# Task_10_1DHD_02_2021-05-30.net
KiCad netlist of a schematic drawn in EasyEDA
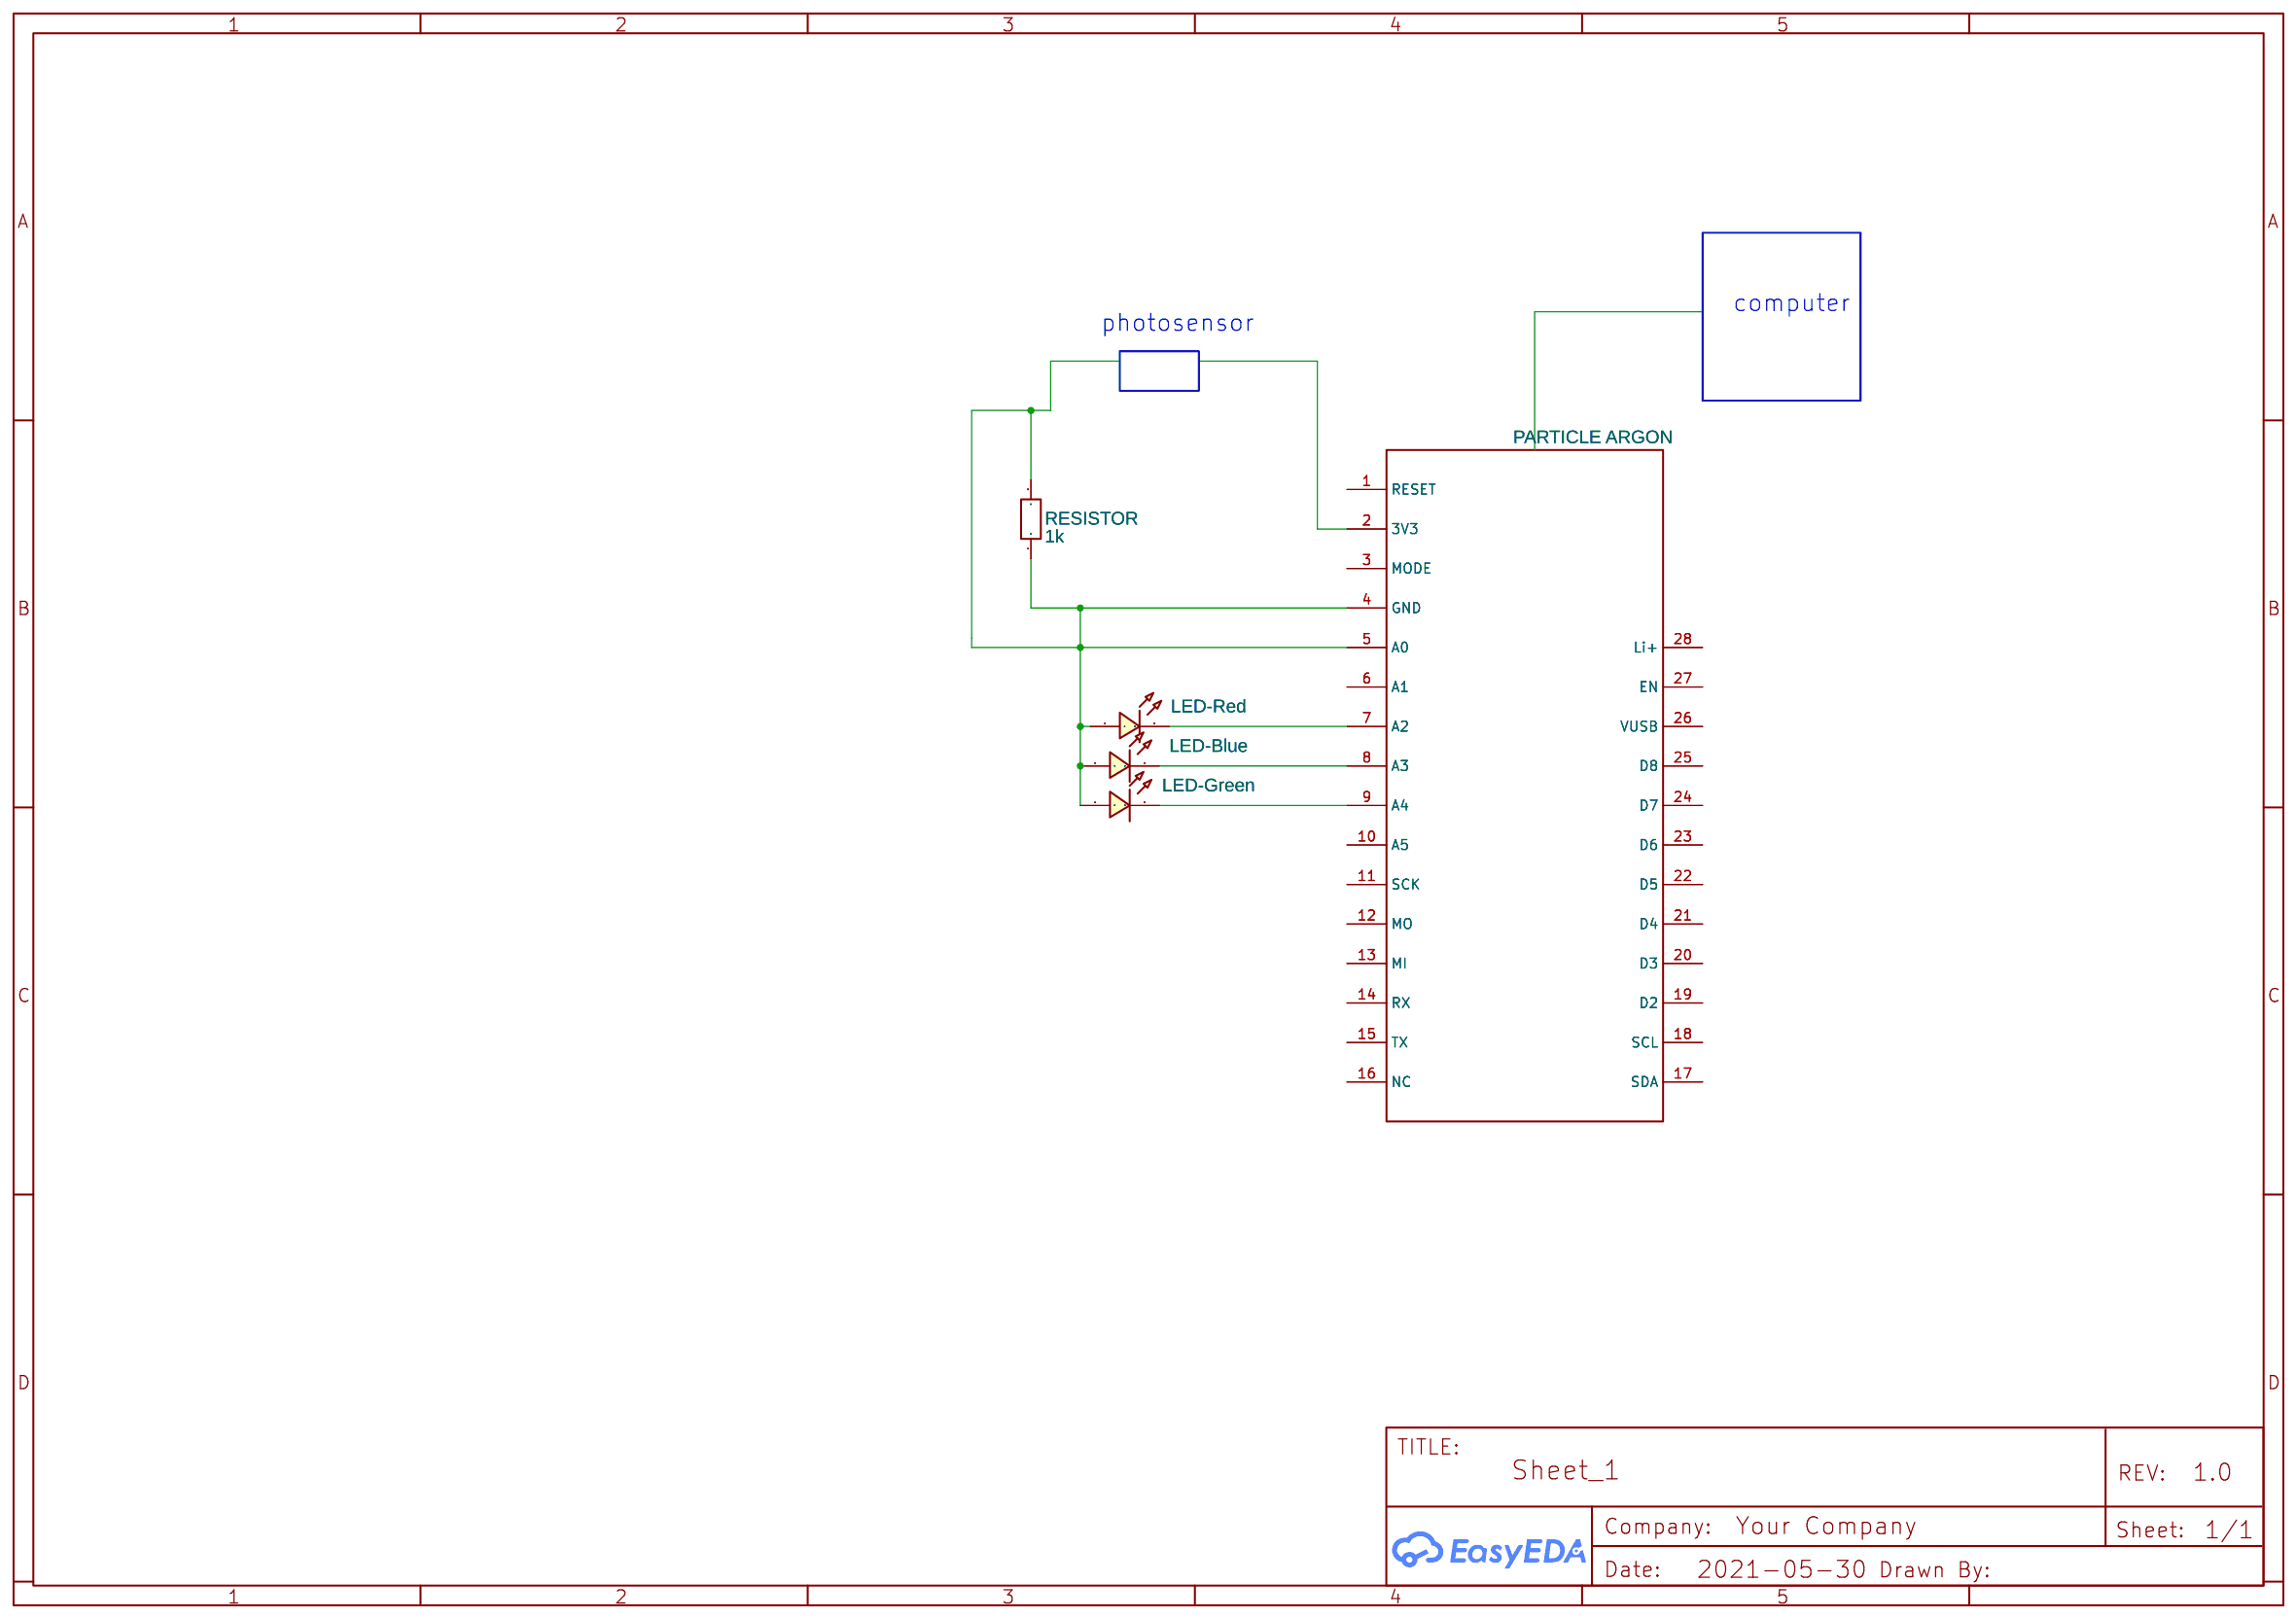
[diagram p0: schematic sheet]

(export (version "E")
  (design (tool "Eeschema 10.0.6"))
  (components
    (comp (ref "LED2")
      (value "LED-Green")
      (fields
        (field (name "BOM_Manufacturer Part") "19-217/R6C-AL1M2VY/3T")
        (field (name "BOM_Supplier Part") "C72044")
      )
      (libsource (lib "") (part "LED-0603_R"))
    )
    (comp (ref "LED3")
      (value "LED-Blue")
      (fields
        (field (name "BOM_Manufacturer Part") "19-217/R6C-AL1M2VY/3T")
        (field (name "BOM_Supplier Part") "C72044")
      )
      (libsource (lib "") (part "LED-0603_R"))
    )
    (comp (ref "LED4")
      (value "LED-Red")
      (fields
        (field (name "BOM_Manufacturer Part") "19-217/R6C-AL1M2VY/3T")
        (field (name "BOM_Supplier Part") "C72044")
      )
      (libsource (lib "") (part "LED-0603_R"))
    )
    (comp (ref "RESISTOR") (value "1k") (libsource (lib "") (part "R_0603_EU")))
    (comp (ref "U1") (value "PARTICLE ARGON") (libsource (lib "") (part "PARTICLE ARGON")))
  )
  (nets
    (net (code "1") (name "Net-(U1-A0)") (class "Default")
      (node (ref "LED2") (pin "1") (pinfunction "1_1") (pintype "unspecified"))
      (node (ref "LED3") (pin "1") (pinfunction "1_1") (pintype "unspecified"))
      (node (ref "LED4") (pin "1") (pinfunction "1_1") (pintype "unspecified"))
      (node (ref "RESISTOR") (pin "1") (pinfunction "1_1") (pintype "unspecified"))
      (node (ref "RESISTOR") (pin "2") (pinfunction "2_2") (pintype "unspecified"))
      (node (ref "U1") (pin "4") (pinfunction "GND_4") (pintype "unspecified"))
      (node (ref "U1") (pin "5") (pinfunction "A0_5") (pintype "unspecified"))
    )
    (net (code "2") (name "Net-(U1-A2)") (class "Default")
      (node (ref "LED4") (pin "2") (pinfunction "2_2") (pintype "unspecified"))
      (node (ref "U1") (pin "7") (pinfunction "A2_7") (pintype "unspecified"))
    )
    (net (code "3") (name "Net-(U1-A3)") (class "Default")
      (node (ref "LED3") (pin "2") (pinfunction "2_2") (pintype "unspecified"))
      (node (ref "U1") (pin "8") (pinfunction "A3_8") (pintype "unspecified"))
    )
    (net (code "4") (name "Net-(U1-A4)") (class "Default")
      (node (ref "LED2") (pin "2") (pinfunction "2_2") (pintype "unspecified"))
      (node (ref "U1") (pin "9") (pinfunction "A4_9") (pintype "unspecified"))
    )
    (net (code "5") (name "unconnected-(U1-3V3-Pad2)") (class "Default")
      (node (ref "U1") (pin "2") (pinfunction "3V3_2") (pintype "unspecified"))
    )
    (net (code "6") (name "unconnected-(U1-A1-Pad6)") (class "Default")
      (node (ref "U1") (pin "6") (pinfunction "A1_6") (pintype "unspecified"))
    )
    (net (code "7") (name "unconnected-(U1-A5-Pad10)") (class "Default")
      (node (ref "U1") (pin "10") (pinfunction "A5_10") (pintype "unspecified"))
    )
    (net (code "8") (name "unconnected-(U1-D2-Pad19)") (class "Default")
      (node (ref "U1") (pin "19") (pinfunction "D2_19") (pintype "unspecified"))
    )
    (net (code "9") (name "unconnected-(U1-D3-Pad20)") (class "Default")
      (node (ref "U1") (pin "20") (pinfunction "D3_20") (pintype "unspecified"))
    )
    (net (code "10") (name "unconnected-(U1-D4-Pad21)") (class "Default")
      (node (ref "U1") (pin "21") (pinfunction "D4_21") (pintype "unspecified"))
    )
    (net (code "11") (name "unconnected-(U1-D5-Pad22)") (class "Default")
      (node (ref "U1") (pin "22") (pinfunction "D5_22") (pintype "unspecified"))
    )
    (net (code "12") (name "unconnected-(U1-D6-Pad23)") (class "Default")
      (node (ref "U1") (pin "23") (pinfunction "D6_23") (pintype "unspecified"))
    )
    (net (code "13") (name "unconnected-(U1-D7-Pad24)") (class "Default")
      (node (ref "U1") (pin "24") (pinfunction "D7_24") (pintype "unspecified"))
    )
    (net (code "14") (name "unconnected-(U1-D8-Pad25)") (class "Default")
      (node (ref "U1") (pin "25") (pinfunction "D8_25") (pintype "unspecified"))
    )
    (net (code "15") (name "unconnected-(U1-EN-Pad27)") (class "Default")
      (node (ref "U1") (pin "27") (pinfunction "EN_27") (pintype "unspecified"))
    )
    (net (code "16") (name "unconnected-(U1-Li+-Pad28)") (class "Default")
      (node (ref "U1") (pin "28") (pinfunction "Li+_28") (pintype "unspecified"))
    )
    (net (code "17") (name "unconnected-(U1-MI-Pad13)") (class "Default")
      (node (ref "U1") (pin "13") (pinfunction "MI_13") (pintype "unspecified"))
    )
    (net (code "18") (name "unconnected-(U1-MO-Pad12)") (class "Default")
      (node (ref "U1") (pin "12") (pinfunction "MO_12") (pintype "unspecified"))
    )
    (net (code "19") (name "unconnected-(U1-MODE-Pad3)") (class "Default")
      (node (ref "U1") (pin "3") (pinfunction "MODE_3") (pintype "unspecified"))
    )
    (net (code "20") (name "unconnected-(U1-NC-Pad16)") (class "Default")
      (node (ref "U1") (pin "16") (pinfunction "NC_16") (pintype "unspecified"))
    )
    (net (code "21") (name "unconnected-(U1-RESET-Pad1)") (class "Default")
      (node (ref "U1") (pin "1") (pinfunction "RESET_1") (pintype "unspecified"))
    )
    (net (code "22") (name "unconnected-(U1-RX-Pad14)") (class "Default")
      (node (ref "U1") (pin "14") (pinfunction "RX_14") (pintype "unspecified"))
    )
    (net (code "23") (name "unconnected-(U1-SCK-Pad11)") (class "Default")
      (node (ref "U1") (pin "11") (pinfunction "SCK_11") (pintype "unspecified"))
    )
    (net (code "24") (name "unconnected-(U1-SCL-Pad18)") (class "Default")
      (node (ref "U1") (pin "18") (pinfunction "SCL_18") (pintype "unspecified"))
    )
    (net (code "25") (name "unconnected-(U1-SDA-Pad17)") (class "Default")
      (node (ref "U1") (pin "17") (pinfunction "SDA_17") (pintype "unspecified"))
    )
    (net (code "26") (name "unconnected-(U1-TX-Pad15)") (class "Default")
      (node (ref "U1") (pin "15") (pinfunction "TX_15") (pintype "unspecified"))
    )
    (net (code "27") (name "unconnected-(U1-VUSB-Pad26)") (class "Default")
      (node (ref "U1") (pin "26") (pinfunction "VUSB_26") (pintype "unspecified"))
    )
  )
)
